# Core.net
KiCad netlist of a schematic drawn in Altium Designer
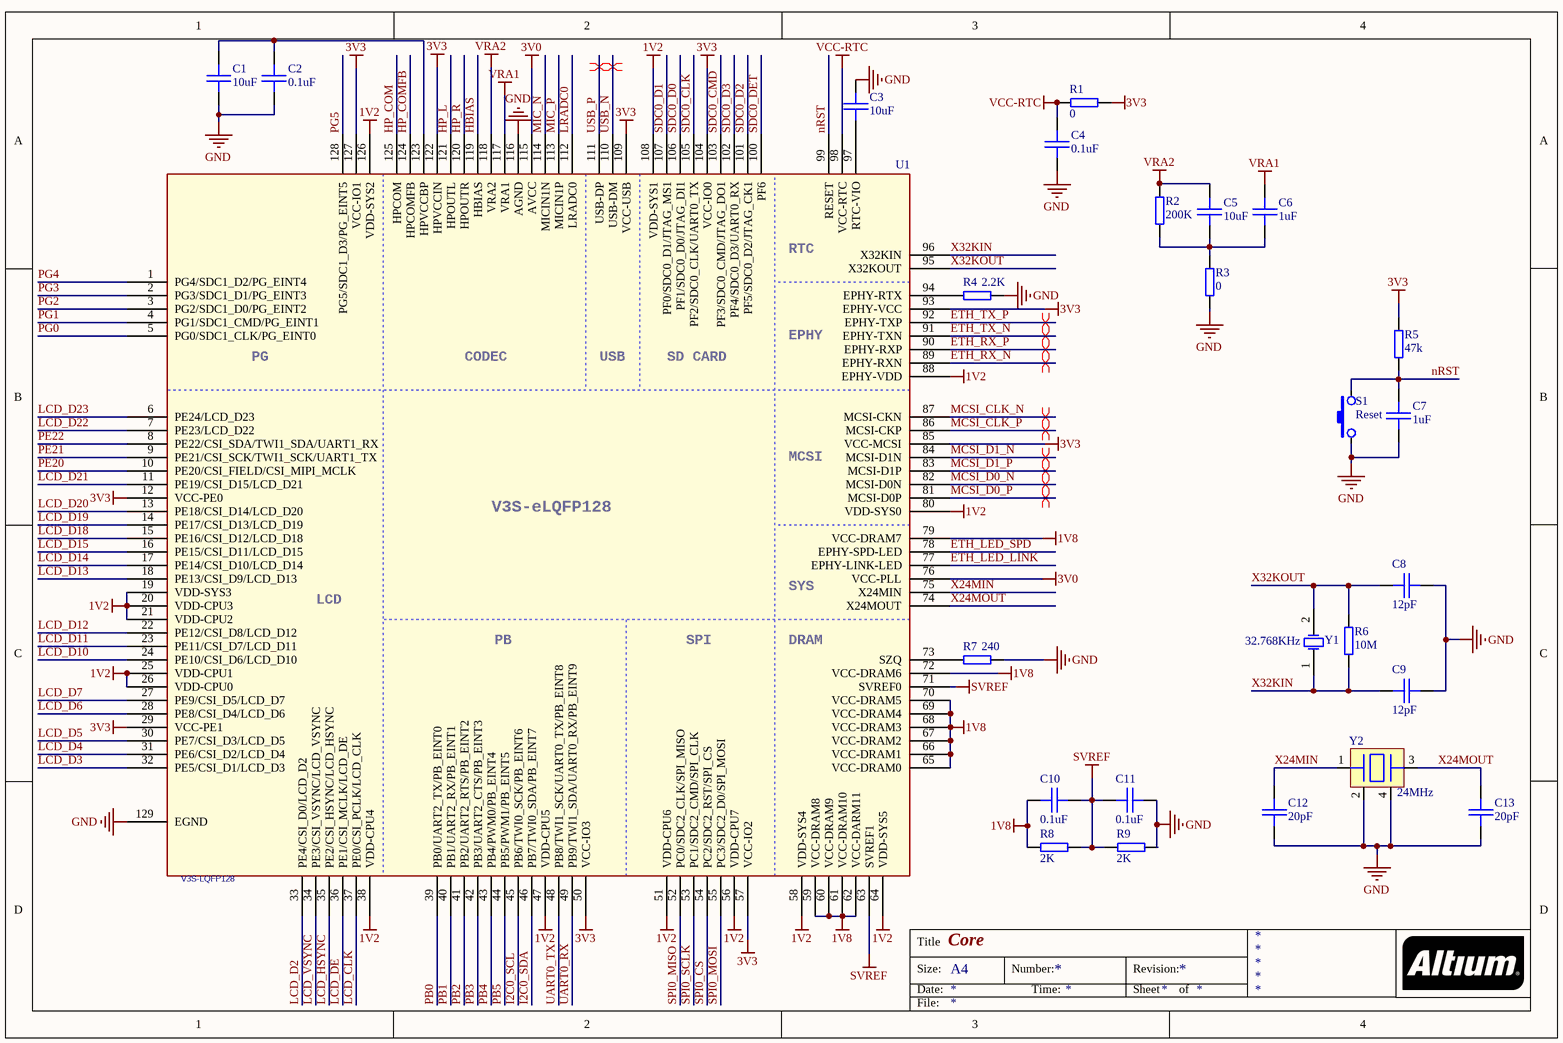
[diagram p0: Core.SchDoc]

(export (version "E")
  (design (tool "Eeschema 10.0.6"))
  (components
    (comp (ref "C1")
      (value "10uF")
      (footprint "CAP-0603")
      (description "陶瓷贴片电容0603")
      (fields (field (name "TOLERANCE") "10%") (field (name "VOLTAGE") "50V"))
      (libsource (lib "momo") (part "C_0603"))
    )
    (comp (ref "C2")
      (value "0.1uF")
      (footprint "CAP-0603")
      (description "陶瓷贴片电容0603")
      (fields (field (name "TOLERANCE") "10%") (field (name "VOLTAGE") "50V"))
      (libsource (lib "momo") (part "C_0603"))
    )
    (comp (ref "C3")
      (value "10uF")
      (footprint "CAP-0603")
      (description "陶瓷贴片电容0603")
      (fields (field (name "TOLERANCE") "10%") (field (name "VOLTAGE") "50V"))
      (libsource (lib "momo") (part "C_0603"))
    )
    (comp (ref "C4")
      (value "0.1uF")
      (footprint "CAP-0603")
      (description "陶瓷贴片电容0603")
      (fields (field (name "TOLERANCE") "10%") (field (name "VOLTAGE") "50V"))
      (libsource (lib "momo") (part "C_0603"))
    )
    (comp (ref "C5")
      (value "10uF")
      (footprint "CAP-0603")
      (description "陶瓷贴片电容0603")
      (fields (field (name "TOLERANCE") "10%") (field (name "VOLTAGE") "50V"))
      (libsource (lib "momo") (part "C_0603"))
    )
    (comp (ref "C6")
      (value "1uF")
      (footprint "CAP-0603")
      (description "陶瓷贴片电容0603")
      (fields (field (name "TOLERANCE") "10%") (field (name "VOLTAGE") "50V"))
      (libsource (lib "momo") (part "C_0603"))
    )
    (comp (ref "C7")
      (value "1uF")
      (footprint "CAP-0603")
      (description "陶瓷贴片电容0603")
      (fields (field (name "TOLERANCE") "10%") (field (name "VOLTAGE") "50V"))
      (libsource (lib "momo") (part "C_0603"))
    )
    (comp (ref "C8")
      (value "12pF")
      (footprint "CAP-0603")
      (description "陶瓷贴片电容0603")
      (fields (field (name "TOLERANCE") "10%") (field (name "VOLTAGE") "50V"))
      (libsource (lib "momo") (part "C_0603"))
    )
    (comp (ref "C9")
      (value "12pF")
      (footprint "CAP-0603")
      (description "陶瓷贴片电容0603")
      (fields (field (name "TOLERANCE") "10%") (field (name "VOLTAGE") "50V"))
      (libsource (lib "momo") (part "C_0603"))
    )
    (comp (ref "C10")
      (value "0.1uF")
      (footprint "CAP-0603")
      (description "陶瓷贴片电容0603")
      (fields (field (name "TOLERANCE") "10%") (field (name "VOLTAGE") "50V"))
      (libsource (lib "momo") (part "C_0603"))
    )
    (comp (ref "C11")
      (value "0.1uF")
      (footprint "CAP-0603")
      (description "陶瓷贴片电容0603")
      (fields (field (name "TOLERANCE") "10%") (field (name "VOLTAGE") "50V"))
      (libsource (lib "momo") (part "C_0603"))
    )
    (comp (ref "C12")
      (value "20pF")
      (footprint "CAP-0603")
      (description "陶瓷贴片电容0603")
      (fields (field (name "TOLERANCE") "10%") (field (name "VOLTAGE") "50V"))
      (libsource (lib "momo") (part "C_0603"))
    )
    (comp (ref "C13")
      (value "20pF")
      (footprint "CAP-0603")
      (description "陶瓷贴片电容0603")
      (fields (field (name "TOLERANCE") "10%") (field (name "VOLTAGE") "50V"))
      (libsource (lib "momo") (part "C_0603"))
    )
    (comp (ref "R1")
      (value "0")
      (footprint "RES-0603")
      (description "贴片电阻0603")
      (fields (field (name "TOLERANCE") "5%") (field (name "VOLTAGE") "50V"))
      (libsource (lib "momo") (part "R_0603"))
    )
    (comp (ref "R2")
      (value "200K")
      (footprint "RES-0603")
      (description "贴片电阻0603")
      (fields (field (name "TOLERANCE") "5%") (field (name "VOLTAGE") "50V"))
      (libsource (lib "momo") (part "R_0603"))
    )
    (comp (ref "R3")
      (value "0")
      (footprint "RES-0603")
      (description "贴片电阻0603")
      (fields (field (name "TOLERANCE") "5%") (field (name "VOLTAGE") "50V"))
      (libsource (lib "momo") (part "R_0603"))
    )
    (comp (ref "R4")
      (value "2.2K")
      (footprint "RES-0603")
      (description "贴片电阻0603")
      (fields (field (name "TOLERANCE") "5%") (field (name "VOLTAGE") "50V"))
      (libsource (lib "momo") (part "R_0603"))
    )
    (comp (ref "R5")
      (value "47k")
      (footprint "RES-0603")
      (description "贴片电阻0603")
      (fields (field (name "TOLERANCE") "5%") (field (name "VOLTAGE") "50V"))
      (libsource (lib "momo") (part "R_0603"))
    )
    (comp (ref "R6")
      (value "10M")
      (footprint "RES-0603")
      (description "贴片电阻0603")
      (fields (field (name "TOLERANCE") "5%") (field (name "VOLTAGE") "50V"))
      (libsource (lib "momo") (part "R_0603"))
    )
    (comp (ref "R7")
      (value "240")
      (footprint "RES-0603")
      (description "贴片电阻0603")
      (fields (field (name "TOLERANCE") "5%") (field (name "VOLTAGE") "50V"))
      (libsource (lib "momo") (part "R_0603"))
    )
    (comp (ref "R8")
      (value "2K")
      (footprint "RES-0603")
      (description "贴片电阻0603")
      (fields (field (name "TOLERANCE") "5%") (field (name "VOLTAGE") "50V"))
      (libsource (lib "momo") (part "R_0603"))
    )
    (comp (ref "R9")
      (value "2K")
      (footprint "RES-0603")
      (description "贴片电阻0603")
      (fields (field (name "TOLERANCE") "5%") (field (name "VOLTAGE") "50V"))
      (libsource (lib "momo") (part "R_0603"))
    )
    (comp (ref "S1")
      (value "Reset")
      (footprint "KEY_3X4X2")
      (description "轻触开关3X4X2")
      (libsource (lib "momo") (part "KEY"))
    )
    (comp (ref "U1")
      (value "V3S-LQFP128")
      (footprint "QFP-128")
      (description "Allwinner V3S SoC")
      (libsource (lib "momo") (part "V3S-LQFP128"))
    )
    (comp (ref "Y1")
      (value "32.768KHz")
      (footprint "FC-135(3215)")
      (description "32.768KHz时钟晶振")
      (libsource (lib "momo") (part "OSC_32768"))
    )
    (comp (ref "Y2")
      (value "24MHz")
      (footprint "LC-SMD-3225_4P")
      (description "贴片无源晶振(3225)")
      (libsource (lib "momo") (part "XTAL_PASSIVE"))
    )
  )
  (nets
    (net (code "1") (name "/ETH_LED_LINK") (class "Default")
      (node (ref "U1") (pin "77") (pinfunction "EPHY-LINK-LED_77") (pintype "passive"))
    )
    (net (code "2") (name "/ETH_LED_SPD") (class "Default")
      (node (ref "U1") (pin "78") (pinfunction "EPHY-SPD-LED_78") (pintype "passive"))
    )
    (net (code "3") (name "/ETH_RX_N") (class "Default")
      (node (ref "U1") (pin "89") (pinfunction "EPHY-RXN_89") (pintype "passive"))
    )
    (net (code "4") (name "/ETH_RX_P") (class "Default")
      (node (ref "U1") (pin "90") (pinfunction "EPHY-RXP_90") (pintype "passive"))
    )
    (net (code "5") (name "/ETH_TX_N") (class "Default")
      (node (ref "U1") (pin "91") (pinfunction "EPHY-TXN_91") (pintype "passive"))
    )
    (net (code "6") (name "/ETH_TX_P") (class "Default")
      (node (ref "U1") (pin "92") (pinfunction "EPHY-TXP_92") (pintype "passive"))
    )
    (net (code "7") (name "/HBIAS") (class "Default")
      (node (ref "U1") (pin "119") (pinfunction "HBIAS_119") (pintype "passive"))
    )
    (net (code "8") (name "/HP_COM") (class "Default")
      (node (ref "U1") (pin "125") (pinfunction "HPCOM_125") (pintype "passive"))
    )
    (net (code "9") (name "/HP_COMFB") (class "Default")
      (node (ref "U1") (pin "124") (pinfunction "HPCOMFB_124") (pintype "passive"))
    )
    (net (code "10") (name "/HP_L") (class "Default")
      (node (ref "U1") (pin "121") (pinfunction "HPOUTL_121") (pintype "passive"))
    )
    (net (code "11") (name "/HP_R") (class "Default")
      (node (ref "U1") (pin "120") (pinfunction "HPOUTR_120") (pintype "passive"))
    )
    (net (code "12") (name "/I2C0_SCL") (class "Default")
      (node (ref "U1") (pin "45") (pinfunction "PB6/TWI0_SCK/PB_EINT6_45") (pintype "passive"))
    )
    (net (code "13") (name "/I2C0_SDA") (class "Default")
      (node (ref "U1") (pin "46") (pinfunction "PB7/TWI0_SDA/PB_EINT7_46") (pintype "passive"))
    )
    (net (code "14") (name "/LCD_CLK") (class "Default")
      (node (ref "U1") (pin "37") (pinfunction "PE0/CSI_PCLK/LCD_CLK_37") (pintype "passive"))
    )
    (net (code "15") (name "/LCD_D2") (class "Default")
      (node (ref "U1") (pin "33") (pinfunction "PE4/CSI_D0/LCD_D2_33") (pintype "passive"))
    )
    (net (code "16") (name "/LCD_D3") (class "Default")
      (node (ref "U1") (pin "32") (pinfunction "PE5/CSI_D1/LCD_D3_32") (pintype "passive"))
    )
    (net (code "17") (name "/LCD_D4") (class "Default")
      (node (ref "U1") (pin "31") (pinfunction "PE6/CSI_D2/LCD_D4_31") (pintype "passive"))
    )
    (net (code "18") (name "/LCD_D5") (class "Default")
      (node (ref "U1") (pin "30") (pinfunction "PE7/CSI_D3/LCD_D5_30") (pintype "passive"))
    )
    (net (code "19") (name "/LCD_D6") (class "Default")
      (node (ref "U1") (pin "28") (pinfunction "PE8/CSI_D4/LCD_D6_28") (pintype "passive"))
    )
    (net (code "20") (name "/LCD_D7") (class "Default")
      (node (ref "U1") (pin "27") (pinfunction "PE9/CSI_D5/LCD_D7_27") (pintype "passive"))
    )
    (net (code "21") (name "/LCD_D10") (class "Default")
      (node (ref "U1") (pin "24") (pinfunction "PE10/CSI_D6/LCD_D10_24") (pintype "passive"))
    )
    (net (code "22") (name "/LCD_D11") (class "Default")
      (node (ref "U1") (pin "23") (pinfunction "PE11/CSI_D7/LCD_D11_23") (pintype "passive"))
    )
    (net (code "23") (name "/LCD_D12") (class "Default")
      (node (ref "U1") (pin "22") (pinfunction "PE12/CSI_D8/LCD_D12_22") (pintype "passive"))
    )
    (net (code "24") (name "/LCD_D13") (class "Default")
      (node (ref "U1") (pin "18") (pinfunction "PE13/CSI_D9/LCD_D13_18") (pintype "passive"))
    )
    (net (code "25") (name "/LCD_D14") (class "Default")
      (node (ref "U1") (pin "17") (pinfunction "PE14/CSI_D10/LCD_D14_17") (pintype "passive"))
    )
    (net (code "26") (name "/LCD_D15") (class "Default")
      (node (ref "U1") (pin "16") (pinfunction "PE15/CSI_D11/LCD_D15_16") (pintype "passive"))
    )
    (net (code "27") (name "/LCD_D18") (class "Default")
      (node (ref "U1") (pin "15") (pinfunction "PE16/CSI_D12/LCD_D18_15") (pintype "passive"))
    )
    (net (code "28") (name "/LCD_D19") (class "Default")
      (node (ref "U1") (pin "14") (pinfunction "PE17/CSI_D13/LCD_D19_14") (pintype "passive"))
    )
    (net (code "29") (name "/LCD_D20") (class "Default")
      (node (ref "U1") (pin "13") (pinfunction "PE18/CSI_D14/LCD_D20_13") (pintype "passive"))
    )
    (net (code "30") (name "/LCD_D21") (class "Default")
      (node (ref "U1") (pin "11") (pinfunction "PE19/CSI_D15/LCD_D21_11") (pintype "passive"))
    )
    (net (code "31") (name "/LCD_D22") (class "Default")
      (node (ref "U1") (pin "7") (pinfunction "PE23/LCD_D22_7") (pintype "passive"))
    )
    (net (code "32") (name "/LCD_D23") (class "Default")
      (node (ref "U1") (pin "6") (pinfunction "PE24/LCD_D23_6") (pintype "passive"))
    )
    (net (code "33") (name "/LCD_DE") (class "Default")
      (node (ref "U1") (pin "36") (pinfunction "PE1/CSI_MCLK/LCD_DE_36") (pintype "passive"))
    )
    (net (code "34") (name "/LCD_HSYNC") (class "Default")
      (node (ref "U1") (pin "35") (pinfunction "PE2/CSI_HSYNC/LCD_HSYNC_35") (pintype "passive"))
    )
    (net (code "35") (name "/LCD_VSYNC") (class "Default")
      (node (ref "U1") (pin "34") (pinfunction "PE3/CSI_VSYNC/LCD_VSYNC_34") (pintype "passive"))
    )
    (net (code "36") (name "/LRADC0") (class "Default")
      (node (ref "U1") (pin "112") (pinfunction "LRADC0_112") (pintype "passive"))
    )
    (net (code "37") (name "/MCSI_CLK_N") (class "Default")
      (node (ref "U1") (pin "87") (pinfunction "MCSI-CKN_87") (pintype "passive"))
    )
    (net (code "38") (name "/MCSI_CLK_P") (class "Default")
      (node (ref "U1") (pin "86") (pinfunction "MCSI-CKP_86") (pintype "passive"))
    )
    (net (code "39") (name "/MCSI_D0_N") (class "Default")
      (node (ref "U1") (pin "82") (pinfunction "MCSI-D0N_82") (pintype "passive"))
    )
    (net (code "40") (name "/MCSI_D0_P") (class "Default")
      (node (ref "U1") (pin "81") (pinfunction "MCSI-D0P_81") (pintype "passive"))
    )
    (net (code "41") (name "/MCSI_D1_N") (class "Default")
      (node (ref "U1") (pin "84") (pinfunction "MCSI-D1N_84") (pintype "passive"))
    )
    (net (code "42") (name "/MCSI_D1_P") (class "Default")
      (node (ref "U1") (pin "83") (pinfunction "MCSI-D1P_83") (pintype "passive"))
    )
    (net (code "43") (name "/MIC_N") (class "Default")
      (node (ref "U1") (pin "114") (pinfunction "MICIN1N_114") (pintype "passive"))
    )
    (net (code "44") (name "/MIC_P") (class "Default")
      (node (ref "U1") (pin "113") (pinfunction "MICIN1P_113") (pintype "passive"))
    )
    (net (code "45") (name "/PB0") (class "Default")
      (node (ref "U1") (pin "39") (pinfunction "PB0/UART2_TX/PB_EINT0_39") (pintype "passive"))
    )
    (net (code "46") (name "/PB1") (class "Default")
      (node (ref "U1") (pin "40") (pinfunction "PB1/UART2_RX/PB_EINT1_40") (pintype "passive"))
    )
    (net (code "47") (name "/PB2") (class "Default")
      (node (ref "U1") (pin "41") (pinfunction "PB2/UART2_RTS/PB_EINT2_41") (pintype "passive"))
    )
    (net (code "48") (name "/PB3") (class "Default")
      (node (ref "U1") (pin "42") (pinfunction "PB3/UART2_CTS/PB_EINT3_42") (pintype "passive"))
    )
    (net (code "49") (name "/PB4") (class "Default")
      (node (ref "U1") (pin "43") (pinfunction "PB4/PWM0/PB_EINT4_43") (pintype "passive"))
    )
    (net (code "50") (name "/PB5") (class "Default")
      (node (ref "U1") (pin "44") (pinfunction "PB5/PWM1/PB_EINT5_44") (pintype "passive"))
    )
    (net (code "51") (name "/PE20") (class "Default")
      (node (ref "U1") (pin "10") (pinfunction "PE20/CSI_FIELD/CSI_MIPI_MCLK_10") (pintype "passive"))
    )
    (net (code "52") (name "/PE21") (class "Default")
      (node (ref "U1") (pin "9") (pinfunction "PE21/CSI_SCK/TWI1_SCK/UART1_TX_9") (pintype "passive"))
    )
    (net (code "53") (name "/PE22") (class "Default")
      (node (ref "U1") (pin "8") (pinfunction "PE22/CSI_SDA/TWI1_SDA/UART1_RX_8") (pintype "passive"))
    )
    (net (code "54") (name "/PG0") (class "Default")
      (node (ref "U1") (pin "5") (pinfunction "PG0/SDC1_CLK/PG_EINT0_5") (pintype "passive"))
    )
    (net (code "55") (name "/PG1") (class "Default")
      (node (ref "U1") (pin "4") (pinfunction "PG1/SDC1_CMD/PG_EINT1_4") (pintype "passive"))
    )
    (net (code "56") (name "/PG2") (class "Default")
      (node (ref "U1") (pin "3") (pinfunction "PG2/SDC1_D0/PG_EINT2_3") (pintype "passive"))
    )
    (net (code "57") (name "/PG3") (class "Default")
      (node (ref "U1") (pin "2") (pinfunction "PG3/SDC1_D1/PG_EINT3_2") (pintype "passive"))
    )
    (net (code "58") (name "/PG4") (class "Default")
      (node (ref "U1") (pin "1") (pinfunction "PG4/SDC1_D2/PG_EINT4_1") (pintype "passive"))
    )
    (net (code "59") (name "/PG5") (class "Default")
      (node (ref "U1") (pin "128") (pinfunction "PG5/SDC1_D3/PG_EINT5_128") (pintype "passive"))
    )
    (net (code "60") (name "/SDC0_CLK") (class "Default")
      (node (ref "U1") (pin "105") (pinfunction "PF2/SDC0_CLK/UART0_TX_105") (pintype "passive"))
    )
    (net (code "61") (name "/SDC0_CMD") (class "Default")
      (node (ref "U1") (pin "103") (pinfunction "PF3/SDC0_CMD/JTAG_DO1_103") (pintype "passive"))
    )
    (net (code "62") (name "/SDC0_D0") (class "Default")
      (node (ref "U1") (pin "106") (pinfunction "PF1/SDC0_D0/JTAG_DI1_106") (pintype "passive"))
    )
    (net (code "63") (name "/SDC0_D1") (class "Default")
      (node (ref "U1") (pin "107") (pinfunction "PF0/SDC0_D1/JTAG_MS1_107") (pintype "passive"))
    )
    (net (code "64") (name "/SDC0_D2") (class "Default")
      (node (ref "U1") (pin "101") (pinfunction "PF5/SDC0_D2/JTAG_CK1_101") (pintype "passive"))
    )
    (net (code "65") (name "/SDC0_D3") (class "Default")
      (node (ref "U1") (pin "102") (pinfunction "PF4/SDC0_D3/UART0_RX_102") (pintype "passive"))
    )
    (net (code "66") (name "/SDC0_DET") (class "Default")
      (node (ref "U1") (pin "100") (pinfunction "PF6_100") (pintype "passive"))
    )
    (net (code "67") (name "/SPI0_CS") (class "Default")
      (node (ref "U1") (pin "54") (pinfunction "PC2/SDC2_RST/SPI_CS_54") (pintype "passive"))
    )
    (net (code "68") (name "/SPI0_MISO") (class "Default")
      (node (ref "U1") (pin "52") (pinfunction "PC0/SDC2_CLK/SPI_MISO_52") (pintype "passive"))
    )
    (net (code "69") (name "/SPI0_MOSI") (class "Default")
      (node (ref "U1") (pin "55") (pinfunction "PC3/SDC2_D0/SPI_MOSI_55") (pintype "passive"))
    )
    (net (code "70") (name "/SPI0_SCLK") (class "Default")
      (node (ref "U1") (pin "53") (pinfunction "PC1/SDC2_CMD/SPI_CLK_53") (pintype "passive"))
    )
    (net (code "71") (name "/UART0_RX") (class "Default")
      (node (ref "U1") (pin "49") (pinfunction "PB9/TWI1_SDA/UART0_RX/PB_EINT9_49") (pintype "passive"))
    )
    (net (code "72") (name "/UART0_TX") (class "Default")
      (node (ref "U1") (pin "48") (pinfunction "PB8/TWI1_SCK/UART0_TX/PB_EINT8_48") (pintype "passive"))
    )
    (net (code "73") (name "/USB_N") (class "Default")
      (node (ref "U1") (pin "110") (pinfunction "USB-DM_110") (pintype "passive"))
    )
    (net (code "74") (name "/USB_P") (class "Default")
      (node (ref "U1") (pin "111") (pinfunction "USB-DP_111") (pintype "passive"))
    )
    (net (code "75") (name "/X24MIN") (class "Default")
      (node (ref "C12") (pin "1") (pinfunction "1_1") (pintype "passive"))
      (node (ref "U1") (pin "75") (pinfunction "X24MIN_75") (pintype "passive"))
      (node (ref "Y2") (pin "1") (pinfunction "1_1") (pintype "passive"))
    )
    (net (code "76") (name "/X24MOUT") (class "Default")
      (node (ref "C13") (pin "1") (pinfunction "1_1") (pintype "passive"))
      (node (ref "U1") (pin "74") (pinfunction "X24MOUT_74") (pintype "passive"))
      (node (ref "Y2") (pin "3") (pinfunction "3_3") (pintype "passive"))
    )
    (net (code "77") (name "/X32KIN") (class "Default")
      (node (ref "C9") (pin "1") (pinfunction "1_1") (pintype "passive"))
      (node (ref "R6") (pin "1") (pinfunction "1_1") (pintype "passive"))
      (node (ref "U1") (pin "96") (pinfunction "X32KIN_96") (pintype "passive"))
      (node (ref "Y1") (pin "1") (pinfunction "OSC1_1") (pintype "passive"))
    )
    (net (code "78") (name "/X32KOUT") (class "Default")
      (node (ref "C8") (pin "1") (pinfunction "1_1") (pintype "passive"))
      (node (ref "R6") (pin "2") (pinfunction "2_2") (pintype "passive"))
      (node (ref "U1") (pin "95") (pinfunction "X32KOUT_95") (pintype "passive"))
      (node (ref "Y1") (pin "2") (pinfunction "OSC2_2") (pintype "passive"))
    )
    (net (code "79") (name "/nRST") (class "Default")
      (node (ref "C7") (pin "1") (pinfunction "1_1") (pintype "passive"))
      (node (ref "R5") (pin "1") (pinfunction "1_1") (pintype "passive"))
      (node (ref "S1") (pin "2") (pinfunction "2_2") (pintype "passive"))
      (node (ref "U1") (pin "99") (pinfunction "RESET_99") (pintype "passive"))
    )
    (net (code "80") (name "1V2") (class "Default")
      (node (ref "U1") (pin "108") (pinfunction "VDD-SYS1_108") (pintype "passive"))
      (node (ref "U1") (pin "126") (pinfunction "VDD-SYS2_126") (pintype "passive"))
      (node (ref "U1") (pin "19") (pinfunction "VDD-SYS3_19") (pintype "passive"))
      (node (ref "U1") (pin "20") (pinfunction "VDD-CPU3_20") (pintype "passive"))
      (node (ref "U1") (pin "21") (pinfunction "VDD-CPU2_21") (pintype "passive"))
      (node (ref "U1") (pin "25") (pinfunction "VDD-CPU1_25") (pintype "passive"))
      (node (ref "U1") (pin "26") (pinfunction "VDD-CPU0_26") (pintype "passive"))
      (node (ref "U1") (pin "38") (pinfunction "VDD-CPU4_38") (pintype "passive"))
      (node (ref "U1") (pin "47") (pinfunction "VDD-CPU5_47") (pintype "passive"))
      (node (ref "U1") (pin "51") (pinfunction "VDD-CPU6_51") (pintype "passive"))
      (node (ref "U1") (pin "56") (pinfunction "VDD-CPU7_56") (pintype "passive"))
      (node (ref "U1") (pin "58") (pinfunction "VDD-SYS4_58") (pintype "passive"))
      (node (ref "U1") (pin "64") (pinfunction "VDD-SYS5_64") (pintype "passive"))
      (node (ref "U1") (pin "80") (pinfunction "VDD-SYS0_80") (pintype "passive"))
      (node (ref "U1") (pin "88") (pinfunction "EPHY-VDD_88") (pintype "passive"))
    )
    (net (code "81") (name "1V8") (class "Default")
      (node (ref "C10") (pin "1") (pinfunction "1_1") (pintype "passive"))
      (node (ref "R8") (pin "1") (pinfunction "1_1") (pintype "passive"))
      (node (ref "U1") (pin "59") (pinfunction "VCC-DRAM8_59") (pintype "passive"))
      (node (ref "U1") (pin "60") (pinfunction "VCC-DRAM9_60") (pintype "passive"))
      (node (ref "U1") (pin "61") (pinfunction "VCC-DRAM10_61") (pintype "passive"))
      (node (ref "U1") (pin "62") (pinfunction "VCC-DARM11_62") (pintype "passive"))
      (node (ref "U1") (pin "65") (pinfunction "VCC-DRAM0_65") (pintype "passive"))
      (node (ref "U1") (pin "66") (pinfunction "VCC-DRAM1_66") (pintype "passive"))
      (node (ref "U1") (pin "67") (pinfunction "VCC-DRAM2_67") (pintype "passive"))
      (node (ref "U1") (pin "68") (pinfunction "VCC-DRAM3_68") (pintype "passive"))
      (node (ref "U1") (pin "69") (pinfunction "VCC-DRAM4_69") (pintype "passive"))
      (node (ref "U1") (pin "70") (pinfunction "VCC-DRAM5_70") (pintype "passive"))
      (node (ref "U1") (pin "72") (pinfunction "VCC-DRAM6_72") (pintype "passive"))
      (node (ref "U1") (pin "79") (pinfunction "VCC-DRAM7_79") (pintype "passive"))
    )
    (net (code "82") (name "3V0") (class "Default")
      (node (ref "U1") (pin "115") (pinfunction "AVCC_115") (pintype "passive"))
      (node (ref "U1") (pin "76") (pinfunction "VCC-PLL_76") (pintype "passive"))
    )
    (net (code "83") (name "3V3") (class "Default")
      (node (ref "R1") (pin "2") (pinfunction "2_2") (pintype "passive"))
      (node (ref "R5") (pin "2") (pinfunction "2_2") (pintype "passive"))
      (node (ref "U1") (pin "104") (pinfunction "VCC-IO0_104") (pintype "passive"))
      (node (ref "U1") (pin "109") (pinfunction "VCC-USB_109") (pintype "passive"))
      (node (ref "U1") (pin "12") (pinfunction "VCC-PE0_12") (pintype "passive"))
      (node (ref "U1") (pin "122") (pinfunction "HPVCCIN_122") (pintype "passive"))
      (node (ref "U1") (pin "127") (pinfunction "VCC-IO1_127") (pintype "passive"))
      (node (ref "U1") (pin "29") (pinfunction "VCC-PE1_29") (pintype "passive"))
      (node (ref "U1") (pin "50") (pinfunction "VCC-IO3_50") (pintype "passive"))
      (node (ref "U1") (pin "57") (pinfunction "VCC-IO2_57") (pintype "passive"))
      (node (ref "U1") (pin "85") (pinfunction "VCC-MCSI_85") (pintype "passive"))
      (node (ref "U1") (pin "93") (pinfunction "EPHY-VCC_93") (pintype "passive"))
    )
    (net (code "84") (name "GND") (class "Default")
      (node (ref "C1") (pin "2") (pinfunction "2_2") (pintype "passive"))
      (node (ref "C11") (pin "2") (pinfunction "2_2") (pintype "passive"))
      (node (ref "C12") (pin "2") (pinfunction "2_2") (pintype "passive"))
      (node (ref "C13") (pin "2") (pinfunction "2_2") (pintype "passive"))
      (node (ref "C2") (pin "2") (pinfunction "2_2") (pintype "passive"))
      (node (ref "C3") (pin "1") (pinfunction "1_1") (pintype "passive"))
      (node (ref "C4") (pin "2") (pinfunction "2_2") (pintype "passive"))
      (node (ref "C7") (pin "2") (pinfunction "2_2") (pintype "passive"))
      (node (ref "C8") (pin "2") (pinfunction "2_2") (pintype "passive"))
      (node (ref "C9") (pin "2") (pinfunction "2_2") (pintype "passive"))
      (node (ref "R3") (pin "1") (pinfunction "1_1") (pintype "passive"))
      (node (ref "R4") (pin "2") (pinfunction "2_2") (pintype "passive"))
      (node (ref "R7") (pin "2") (pinfunction "2_2") (pintype "passive"))
      (node (ref "R9") (pin "2") (pinfunction "2_2") (pintype "passive"))
      (node (ref "S1") (pin "1") (pinfunction "1_1") (pintype "passive"))
      (node (ref "U1") (pin "116") (pinfunction "AGND_116") (pintype "passive"))
      (node (ref "U1") (pin "129") (pinfunction "EGND_129") (pintype "passive"))
      (node (ref "Y2") (pin "2") (pinfunction "2_2") (pintype "passive"))
      (node (ref "Y2") (pin "4") (pinfunction "4_4") (pintype "passive"))
    )
    (net (code "85") (name "Net-(C5-Pad2)") (class "Default")
      (node (ref "C5") (pin "2") (pinfunction "2_2") (pintype "passive"))
      (node (ref "C6") (pin "2") (pinfunction "2_2") (pintype "passive"))
      (node (ref "R2") (pin "1") (pinfunction "1_1") (pintype "passive"))
      (node (ref "R3") (pin "2") (pinfunction "2_2") (pintype "passive"))
    )
    (net (code "86") (name "Net-(U1-EPHY-RTX)") (class "Default")
      (node (ref "R4") (pin "1") (pinfunction "1_1") (pintype "passive"))
      (node (ref "U1") (pin "94") (pinfunction "EPHY-RTX_94") (pintype "passive"))
    )
    (net (code "87") (name "Net-(U1-HPVCCBP)") (class "Default")
      (node (ref "C1") (pin "1") (pinfunction "1_1") (pintype "passive"))
      (node (ref "C2") (pin "1") (pinfunction "1_1") (pintype "passive"))
      (node (ref "U1") (pin "123") (pinfunction "HPVCCBP_123") (pintype "passive"))
    )
    (net (code "88") (name "Net-(U1-RTC-VIO)") (class "Default")
      (node (ref "C3") (pin "2") (pinfunction "2_2") (pintype "passive"))
      (node (ref "U1") (pin "97") (pinfunction "RTC-VIO_97") (pintype "passive"))
    )
    (net (code "89") (name "Net-(U1-SZQ)") (class "Default")
      (node (ref "R7") (pin "1") (pinfunction "1_1") (pintype "passive"))
      (node (ref "U1") (pin "73") (pinfunction "SZQ_73") (pintype "passive"))
    )
    (net (code "90") (name "SVREF") (class "Default")
      (node (ref "C10") (pin "2") (pinfunction "2_2") (pintype "passive"))
      (node (ref "C11") (pin "1") (pinfunction "1_1") (pintype "passive"))
      (node (ref "R8") (pin "2") (pinfunction "2_2") (pintype "passive"))
      (node (ref "R9") (pin "1") (pinfunction "1_1") (pintype "passive"))
      (node (ref "U1") (pin "63") (pinfunction "SVREF1_63") (pintype "passive"))
      (node (ref "U1") (pin "71") (pinfunction "SVREF0_71") (pintype "passive"))
    )
    (net (code "91") (name "VCC-RTC") (class "Default")
      (node (ref "C4") (pin "1") (pinfunction "1_1") (pintype "passive"))
      (node (ref "R1") (pin "1") (pinfunction "1_1") (pintype "passive"))
      (node (ref "U1") (pin "98") (pinfunction "VCC-RTC_98") (pintype "passive"))
    )
    (net (code "92") (name "VRA1") (class "Default")
      (node (ref "C6") (pin "1") (pinfunction "1_1") (pintype "passive"))
      (node (ref "U1") (pin "117") (pinfunction "VRA1_117") (pintype "passive"))
    )
    (net (code "93") (name "VRA2") (class "Default")
      (node (ref "C5") (pin "1") (pinfunction "1_1") (pintype "passive"))
      (node (ref "R2") (pin "2") (pinfunction "2_2") (pintype "passive"))
      (node (ref "U1") (pin "118") (pinfunction "VRA2_118") (pintype "passive"))
    )
  )
)
